# transAmpV1_sch.net
KiCad netlist of a schematic drawn in Altium Designer
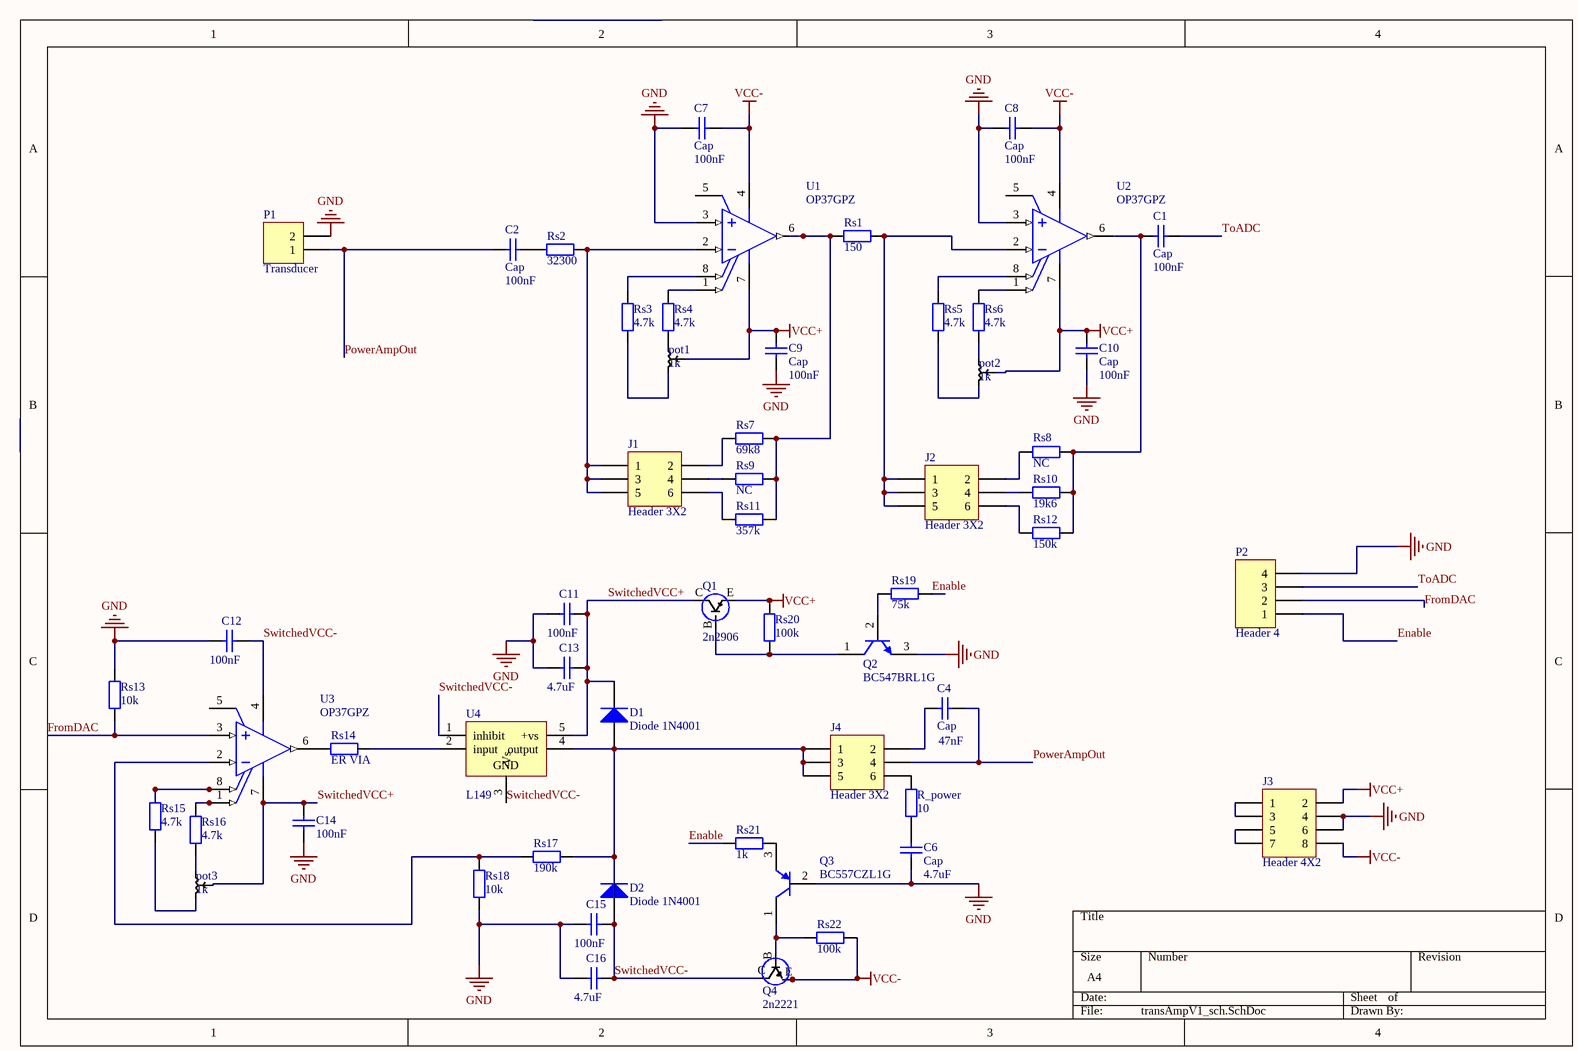
[diagram p0: transAmpV1_sch.SchDoc]

(export (version "E")
  (design (tool "Eeschema 10.0.6"))
  (components
    (comp (ref "C1")
      (value "Cap")
      (footprint "RAD-0.2  PCBK")
      (description "Capacitor")
      (fields (field (name "ALTIUM_VALUE") "100nF") (field (name "PUBLISHER") "Altium Limited"))
      (libsource (lib "pcb_kursus_lib2020") (part "Cap PCBK"))
    )
    (comp (ref "C2")
      (value "Cap")
      (footprint "RAD-0.2  PCBK")
      (description "Capacitor")
      (fields (field (name "ALTIUM_VALUE") "100nF") (field (name "PUBLISHER") "Altium Limited"))
      (libsource (lib "pcb_kursus_lib2020") (part "Cap PCBK"))
    )
    (comp (ref "C4")
      (value "Cap")
      (footprint "RAD-0.2  PCBK")
      (description "Capacitor")
      (fields (field (name "ALTIUM_VALUE") "47nF") (field (name "PUBLISHER") "Altium Limited"))
      (libsource (lib "pcb_kursus_lib2020") (part "Cap PCBK"))
    )
    (comp (ref "C6")
      (value "Cap")
      (footprint "RAD-0.2  PCBK")
      (description "Capacitor")
      (fields (field (name "ALTIUM_VALUE") "4.7uF") (field (name "PUBLISHER") "Altium Limited"))
      (libsource (lib "pcb_kursus_lib2020") (part "Cap PCBK"))
    )
    (comp (ref "C7")
      (value "Cap")
      (footprint "RAD-0.2  PCBK")
      (description "Capacitor")
      (fields (field (name "ALTIUM_VALUE") "100nF") (field (name "PUBLISHER") "Altium Limited"))
      (libsource (lib "pcb_kursus_lib2020") (part "Cap PCBK"))
    )
    (comp (ref "C8")
      (value "Cap")
      (footprint "RAD-0.2  PCBK")
      (description "Capacitor")
      (fields (field (name "ALTIUM_VALUE") "100nF") (field (name "PUBLISHER") "Altium Limited"))
      (libsource (lib "pcb_kursus_lib2020") (part "Cap PCBK"))
    )
    (comp (ref "C9")
      (value "Cap")
      (footprint "RAD-0.2  PCBK")
      (description "Capacitor")
      (fields (field (name "ALTIUM_VALUE") "100nF") (field (name "PUBLISHER") "Altium Limited"))
      (libsource (lib "pcb_kursus_lib2020") (part "Cap PCBK"))
    )
    (comp (ref "C10")
      (value "Cap")
      (footprint "RAD-0.2  PCBK")
      (description "Capacitor")
      (fields (field (name "ALTIUM_VALUE") "100nF") (field (name "PUBLISHER") "Altium Limited"))
      (libsource (lib "pcb_kursus_lib2020") (part "Cap PCBK"))
    )
    (comp (ref "C11")
      (value "100nF")
      (footprint "RAD-0.2  PCBK")
      (description "Capacitor")
      (fields (field (name "Comment") "Cap") (field (name "PUBLISHER") "Altium Limited"))
      (libsource (lib "pcb_kursus_lib2020") (part "Cap PCBK"))
    )
    (comp (ref "C12")
      (value "100nF")
      (footprint "RAD-0.2  PCBK")
      (description "Capacitor")
      (fields (field (name "Comment") "Cap") (field (name "PUBLISHER") "Altium Limited"))
      (libsource (lib "pcb_kursus_lib2020") (part "Cap PCBK"))
    )
    (comp (ref "C13")
      (value "4.7uF")
      (footprint "RAD-0.2  PCBK")
      (description "Capacitor")
      (fields (field (name "Comment") "Cap") (field (name "PUBLISHER") "Altium Limited"))
      (libsource (lib "pcb_kursus_lib2020") (part "Cap PCBK"))
    )
    (comp (ref "C14")
      (value "100nF")
      (footprint "RAD-0.2  PCBK")
      (description "Capacitor")
      (fields (field (name "Comment") "Cap") (field (name "PUBLISHER") "Altium Limited"))
      (libsource (lib "pcb_kursus_lib2020") (part "Cap PCBK"))
    )
    (comp (ref "C15")
      (value "100nF")
      (footprint "RAD-0.2  PCBK")
      (description "Capacitor")
      (fields (field (name "Comment") "Cap") (field (name "PUBLISHER") "Altium Limited"))
      (libsource (lib "pcb_kursus_lib2020") (part "Cap PCBK"))
    )
    (comp (ref "C16")
      (value "4.7uF")
      (footprint "RAD-0.2  PCBK")
      (description "Capacitor")
      (fields (field (name "Comment") "Cap") (field (name "PUBLISHER") "Altium Limited"))
      (libsource (lib "pcb_kursus_lib2020") (part "Cap PCBK"))
    )
    (comp (ref "D1")
      (value "Diode 1N4001")
      (footprint "DO-41")
      (description "1 Amp General Purpose Rectifier")
      (fields (field (name "PUBLISHER") "Altium Limited"))
      (libsource (lib "Miscellaneous Devices") (part "Diode 1N4001"))
    )
    (comp (ref "D2")
      (value "Diode 1N4001")
      (footprint "DO-41")
      (description "1 Amp General Purpose Rectifier")
      (fields (field (name "PUBLISHER") "Altium Limited"))
      (libsource (lib "Miscellaneous Devices") (part "Diode 1N4001"))
    )
    (comp (ref "J1")
      (value "Header 3X2")
      (footprint "HDR2X3 PCBK")
      (description "Header, 3-Pin, Dual row")
      (fields (field (name "PUBLISHER") "Altium Limited"))
      (libsource (lib "pcb_kursus_lib2020") (part "Header 3X2 PBCK"))
    )
    (comp (ref "J2")
      (value "Header 3X2")
      (footprint "HDR2X3 PCBK")
      (description "Header, 3-Pin, Dual row")
      (fields (field (name "PUBLISHER") "Altium Limited"))
      (libsource (lib "pcb_kursus_lib2020") (part "Header 3X2 PBCK"))
    )
    (comp (ref "J3")
      (value "Header 4X2")
      (footprint "HDR2X4 PCBK")
      (description "Header, 4-Pin, Dual row")
      (fields (field (name "PUBLISHER") "Altium Limited"))
      (libsource (lib "pcb_kursus_lib2020") (part "Header 4X2 PBCK"))
    )
    (comp (ref "J4")
      (value "Header 3X2")
      (footprint "HDR2X3 PCBK")
      (description "Header, 3-Pin, Dual row")
      (fields (field (name "PUBLISHER") "Altium Limited"))
      (libsource (lib "pcb_kursus_lib2020") (part "Header 3X2 PBCK"))
    )
    (comp (ref "P1")
      (value "Transducer")
      (footprint "HDR1X2")
      (description "Header, 2-Pin")
      (fields (field (name "PUBLISHER") "Altium Limited"))
      (libsource (lib "Miscellaneous Connectors") (part "Header 2"))
    )
    (comp (ref "P2")
      (value "Header 4")
      (footprint "HDR1X4")
      (description "Header, 4-Pin")
      (fields (field (name "PUBLISHER") "Altium Limited"))
      (libsource (lib "Miscellaneous Connectors") (part "Header 4"))
    )
    (comp (ref "pot1")
      (value "1k")
      (footprint "potMeter_3328P")
      (libsource (lib "WatsonInt_Lib") (part "TrimPotOpAmp"))
    )
    (comp (ref "pot2")
      (value "1k")
      (footprint "potMeter_3328P")
      (libsource (lib "WatsonInt_Lib") (part "TrimPotOpAmp"))
    )
    (comp (ref "pot3")
      (value "1k")
      (footprint "potMeter_3328P")
      (libsource (lib "WatsonInt_Lib") (part "TrimPotOpAmp"))
    )
    (comp (ref "Q1") (value "2n2906") (footprint "TO-18") (libsource (lib "WatsonInt_Lib") (part "2n2906")))
    (comp (ref "Q2")
      (value "BC547BRL1G")
      (footprint "ONSC-TO-92-3-29-11_AM_BL")
      (description "Amplifier Transistor, NPN Silicon, 3-Pin TO-92, Pb-Free, Tape and Reel")
      (fields (field (name "MANUFACTURER") "On Semiconductor"))
      (libsource (lib "Altium Content Vault") (part "ONSC-NPN-C1B2E3-3"))
    )
    (comp (ref "Q3")
      (value "BC557CZL1G")
      (footprint "ONSC-TO-92-3-29-11_AM_BL")
      (description "Amplifier Transistor, PNP Silicon, 3-Pin TO-92, Pb-Free, Ammo Box")
      (fields (field (name "MANUFACTURER") "On Semiconductor"))
      (libsource (lib "Altium Content Vault") (part "ONSC-PNP-C1B2E3-3"))
    )
    (comp (ref "Q4") (value "2n2221") (footprint "TO-18") (libsource (lib "WatsonInt_Lib") (part "2n2221")))
    (comp (ref "Rs1")
      (value "150")
      (footprint "AXIAL-0.4 PCBK")
      (description "Resistor")
      (fields (field (name "PUBLISHER") "Altium Limited"))
      (libsource (lib "pcb_kursus_lib2020") (part "Res PCBK"))
    )
    (comp (ref "Rs2")
      (value "32300")
      (footprint "AXIAL-0.4 PCBK")
      (description "Resistor")
      (fields (field (name "PUBLISHER") "Altium Limited"))
      (libsource (lib "pcb_kursus_lib2020") (part "Res PCBK"))
    )
    (comp (ref "Rs3")
      (value "4.7k")
      (footprint "AXIAL-0.4 PCBK")
      (description "Resistor")
      (fields (field (name "PUBLISHER") "Altium Limited"))
      (libsource (lib "") (part "Res PCBK_1"))
    )
    (comp (ref "Rs4")
      (value "4.7k")
      (footprint "AXIAL-0.4 PCBK")
      (description "Resistor")
      (fields (field (name "PUBLISHER") "Altium Limited"))
      (libsource (lib "") (part "Res PCBK_1"))
    )
    (comp (ref "Rs5")
      (value "4.7k")
      (footprint "AXIAL-0.4 PCBK")
      (description "Resistor")
      (fields (field (name "PUBLISHER") "Altium Limited"))
      (libsource (lib "") (part "Res PCBK_1"))
    )
    (comp (ref "Rs6")
      (value "4.7k")
      (footprint "AXIAL-0.4 PCBK")
      (description "Resistor")
      (fields (field (name "PUBLISHER") "Altium Limited"))
      (libsource (lib "") (part "Res PCBK_1"))
    )
    (comp (ref "Rs7")
      (value "69k8")
      (footprint "AXIAL-0.4 PCBK")
      (description "Resistor")
      (fields (field (name "PUBLISHER") "Altium Limited"))
      (libsource (lib "pcb_kursus_lib2020") (part "Res PCBK"))
    )
    (comp (ref "Rs8")
      (value "NC")
      (footprint "AXIAL-0.4 PCBK")
      (description "Resistor")
      (fields (field (name "PUBLISHER") "Altium Limited"))
      (libsource (lib "pcb_kursus_lib2020") (part "Res PCBK"))
    )
    (comp (ref "Rs9")
      (value "NC")
      (footprint "AXIAL-0.4 PCBK")
      (description "Resistor")
      (fields (field (name "PUBLISHER") "Altium Limited"))
      (libsource (lib "pcb_kursus_lib2020") (part "Res PCBK"))
    )
    (comp (ref "Rs10")
      (value "19k6")
      (footprint "AXIAL-0.4 PCBK")
      (description "Resistor")
      (fields (field (name "PUBLISHER") "Altium Limited"))
      (libsource (lib "pcb_kursus_lib2020") (part "Res PCBK"))
    )
    (comp (ref "Rs11")
      (value "357k")
      (footprint "AXIAL-0.4 PCBK")
      (description "Resistor")
      (fields (field (name "PUBLISHER") "Altium Limited"))
      (libsource (lib "pcb_kursus_lib2020") (part "Res PCBK"))
    )
    (comp (ref "Rs12")
      (value "150k")
      (footprint "AXIAL-0.4 PCBK")
      (description "Resistor")
      (fields (field (name "PUBLISHER") "Altium Limited"))
      (libsource (lib "pcb_kursus_lib2020") (part "Res PCBK"))
    )
    (comp (ref "Rs13")
      (value "10k")
      (footprint "AXIAL-0.4 PCBK")
      (description "Resistor")
      (fields (field (name "PUBLISHER") "Altium Limited"))
      (libsource (lib "") (part "Res PCBK_2"))
    )
    (comp (ref "Rs14")
      (value "ER VIA")
      (footprint "AXIAL-0.4 PCBK")
      (description "Resistor")
      (fields (field (name "PUBLISHER") "Altium Limited"))
      (libsource (lib "pcb_kursus_lib2020") (part "Res PCBK"))
    )
    (comp (ref "Rs15")
      (value "4.7k")
      (footprint "AXIAL-0.4 PCBK")
      (description "Resistor")
      (fields (field (name "PUBLISHER") "Altium Limited"))
      (libsource (lib "") (part "Res PCBK_1"))
    )
    (comp (ref "Rs16")
      (value "4.7k")
      (footprint "AXIAL-0.4 PCBK")
      (description "Resistor")
      (fields (field (name "PUBLISHER") "Altium Limited"))
      (libsource (lib "") (part "Res PCBK_1"))
    )
    (comp (ref "Rs17")
      (value "190k")
      (footprint "AXIAL-0.4 PCBK")
      (description "Resistor")
      (fields (field (name "PUBLISHER") "Altium Limited"))
      (libsource (lib "pcb_kursus_lib2020") (part "Res PCBK"))
    )
    (comp (ref "Rs18")
      (value "10k")
      (footprint "AXIAL-0.4 PCBK")
      (description "Resistor")
      (fields (field (name "PUBLISHER") "Altium Limited"))
      (libsource (lib "") (part "Res PCBK_2"))
    )
    (comp (ref "Rs19")
      (value "75k")
      (footprint "AXIAL-0.4 PCBK")
      (description "Resistor")
      (fields (field (name "PUBLISHER") "Altium Limited"))
      (libsource (lib "pcb_kursus_lib2020") (part "Res PCBK"))
    )
    (comp (ref "Rs20")
      (value "100k")
      (footprint "AXIAL-0.4 PCBK")
      (description "Resistor")
      (fields (field (name "PUBLISHER") "Altium Limited"))
      (libsource (lib "") (part "Res PCBK_1"))
    )
    (comp (ref "Rs21")
      (value "1k")
      (footprint "AXIAL-0.4 PCBK")
      (description "Resistor")
      (fields (field (name "PUBLISHER") "Altium Limited"))
      (libsource (lib "pcb_kursus_lib2020") (part "Res PCBK"))
    )
    (comp (ref "Rs22")
      (value "100k")
      (footprint "AXIAL-0.4 PCBK")
      (description "Resistor")
      (fields (field (name "PUBLISHER") "Altium Limited"))
      (libsource (lib "") (part "Res PCBK_3"))
    )
    (comp (ref "R_power")
      (value "10")
      (footprint "AXIAL-0.4 PCBK")
      (description "Resistor")
      (fields (field (name "PUBLISHER") "Altium Limited"))
      (libsource (lib "") (part "Res PCBK_2"))
    )
    (comp (ref "U1")
      (value "OP37GPZ")
      (footprint "ADI-N-8")
      (fields (field (name "GENERIC PART NUMBER") "OP37") (field (name "MANUFACTURER") "Analog Devices"))
      (libsource (lib "Altium Content Vault") (part "ADI-OP177_X7-8"))
    )
    (comp (ref "U2")
      (value "OP37GPZ")
      (footprint "ADI-N-8")
      (fields (field (name "GENERIC PART NUMBER") "OP37") (field (name "MANUFACTURER") "Analog Devices"))
      (libsource (lib "Altium Content Vault") (part "ADI-OP177_X7-8"))
    )
    (comp (ref "U3")
      (value "OP37GPZ")
      (footprint "ADI-N-8")
      (fields (field (name "GENERIC PART NUMBER") "OP37") (field (name "MANUFACTURER") "Analog Devices"))
      (libsource (lib "Altium Content Vault") (part "ADI-OP177_X7-8"))
    )
    (comp (ref "U4")
      (value "L149")
      (footprint "PentawattV")
      (description "Adjustable Voltage and Current Regulator, 5-Pin Pentawatt, Tube")
      (libsource (lib "Altium Content Vault") (part "PM-REG-L200-ZIL5"))
    )
  )
  (nets
    (net (code "1") (name "/Enable") (class "Default")
      (node (ref "P2") (pin "1") (pinfunction "1_1") (pintype "passive"))
      (node (ref "Rs19") (pin "1") (pinfunction "1_1") (pintype "passive"))
      (node (ref "Rs21") (pin "2") (pinfunction "2_2") (pintype "passive"))
    )
    (net (code "2") (name "/FromDAC") (class "Default")
      (node (ref "P2") (pin "2") (pinfunction "2_2") (pintype "passive"))
      (node (ref "Rs13") (pin "2") (pinfunction "2_2") (pintype "passive"))
      (node (ref "U3") (pin "3") (pinfunction "+IN_3") (pintype "input"))
    )
    (net (code "3") (name "/PowerAmpOut") (class "Default")
      (node (ref "C2") (pin "1") (pinfunction "1_1") (pintype "passive"))
      (node (ref "C4") (pin "2") (pinfunction "2_2") (pintype "passive"))
      (node (ref "J4") (pin "4") (pinfunction "4_4") (pintype "passive"))
      (node (ref "P1") (pin "1") (pinfunction "1_1") (pintype "passive"))
    )
    (net (code "4") (name "/SwitchedVCC+") (class "Default")
      (node (ref "C11") (pin "2") (pinfunction "2_2") (pintype "passive"))
      (node (ref "C13") (pin "2") (pinfunction "2_2") (pintype "passive"))
      (node (ref "C14") (pin "2") (pinfunction "2_2") (pintype "passive"))
      (node (ref "D1") (pin "2") (pinfunction "K_2") (pintype "passive"))
      (node (ref "Q1") (pin "C") (pinfunction "22_C") (pintype "passive"))
      (node (ref "U3") (pin "7") (pinfunction "V+_7") (pintype "power_in"))
      (node (ref "U4") (pin "5") (pinfunction "+vs_5") (pintype "power_in"))
      (node (ref "pot3") (pin "2") (pinfunction "2_2") (pintype "passive"))
    )
    (net (code "5") (name "/SwitchedVCC-") (class "Default")
      (node (ref "C12") (pin "2") (pinfunction "2_2") (pintype "passive"))
      (node (ref "C15") (pin "2") (pinfunction "2_2") (pintype "passive"))
      (node (ref "C16") (pin "2") (pinfunction "2_2") (pintype "passive"))
      (node (ref "D2") (pin "1") (pinfunction "A_1") (pintype "passive"))
      (node (ref "Q4") (pin "C") (pinfunction "23_C") (pintype "passive"))
      (node (ref "U3") (pin "4") (pinfunction "V-_4") (pintype "power_in"))
      (node (ref "U4") (pin "1") (pinfunction "inhibit_1") (pintype "power_in"))
      (node (ref "U4") (pin "3") (pinfunction "-Vs_3") (pintype "power_in"))
    )
    (net (code "6") (name "/ToADC") (class "Default")
      (node (ref "C1") (pin "2") (pinfunction "2_2") (pintype "passive"))
      (node (ref "P2") (pin "3") (pinfunction "3_3") (pintype "passive"))
    )
    (net (code "7") (name "GND") (class "Default")
      (node (ref "C10") (pin "2") (pinfunction "2_2") (pintype "passive"))
      (node (ref "C11") (pin "1") (pinfunction "1_1") (pintype "passive"))
      (node (ref "C12") (pin "1") (pinfunction "1_1") (pintype "passive"))
      (node (ref "C13") (pin "1") (pinfunction "1_1") (pintype "passive"))
      (node (ref "C14") (pin "1") (pinfunction "1_1") (pintype "passive"))
      (node (ref "C15") (pin "1") (pinfunction "1_1") (pintype "passive"))
      (node (ref "C16") (pin "1") (pinfunction "1_1") (pintype "passive"))
      (node (ref "C6") (pin "2") (pinfunction "2_2") (pintype "passive"))
      (node (ref "C7") (pin "1") (pinfunction "1_1") (pintype "passive"))
      (node (ref "C8") (pin "1") (pinfunction "1_1") (pintype "passive"))
      (node (ref "C9") (pin "2") (pinfunction "2_2") (pintype "passive"))
      (node (ref "J3") (pin "4") (pinfunction "4_4") (pintype "passive"))
      (node (ref "J3") (pin "6") (pinfunction "6_6") (pintype "passive"))
      (node (ref "P1") (pin "2") (pinfunction "2_2") (pintype "passive"))
      (node (ref "P2") (pin "4") (pinfunction "4_4") (pintype "passive"))
      (node (ref "Q2") (pin "3") (pinfunction "E_3") (pintype "passive"))
      (node (ref "Q3") (pin "2") (pinfunction "B_2") (pintype "passive"))
      (node (ref "Rs13") (pin "1") (pinfunction "1_1") (pintype "passive"))
      (node (ref "Rs18") (pin "2") (pinfunction "2_2") (pintype "passive"))
      (node (ref "U1") (pin "3") (pinfunction "+IN_3") (pintype "input"))
      (node (ref "U2") (pin "3") (pinfunction "+IN_3") (pintype "input"))
    )
    (net (code "8") (name "Net-(C2-Pad2)") (class "Default")
      (node (ref "C2") (pin "2") (pinfunction "2_2") (pintype "passive"))
      (node (ref "Rs2") (pin "2") (pinfunction "2_2") (pintype "passive"))
    )
    (net (code "9") (name "Net-(C4-Pad1)") (class "Default")
      (node (ref "C4") (pin "1") (pinfunction "1_1") (pintype "passive"))
      (node (ref "J4") (pin "2") (pinfunction "2_2") (pintype "passive"))
    )
    (net (code "10") (name "Net-(C6-Pad1)") (class "Default")
      (node (ref "C6") (pin "1") (pinfunction "1_1") (pintype "passive"))
      (node (ref "R_power") (pin "2") (pinfunction "2_2") (pintype "passive"))
    )
    (net (code "11") (name "Net-(D1-A)") (class "Default")
      (node (ref "D1") (pin "1") (pinfunction "A_1") (pintype "passive"))
      (node (ref "D2") (pin "2") (pinfunction "K_2") (pintype "passive"))
      (node (ref "J4") (pin "1") (pinfunction "1_1") (pintype "passive"))
      (node (ref "J4") (pin "3") (pinfunction "3_3") (pintype "passive"))
      (node (ref "J4") (pin "5") (pinfunction "5_5") (pintype "passive"))
      (node (ref "Rs17") (pin "1") (pinfunction "1_1") (pintype "passive"))
      (node (ref "U4") (pin "4") (pinfunction "output_4") (pintype "passive"))
    )
    (net (code "12") (name "Net-(J1-Pad2)") (class "Default")
      (node (ref "J1") (pin "2") (pinfunction "2_2") (pintype "passive"))
      (node (ref "Rs7") (pin "2") (pinfunction "2_2") (pintype "passive"))
    )
    (net (code "13") (name "Net-(J1-Pad4)") (class "Default")
      (node (ref "J1") (pin "4") (pinfunction "4_4") (pintype "passive"))
      (node (ref "Rs9") (pin "2") (pinfunction "2_2") (pintype "passive"))
    )
    (net (code "14") (name "Net-(J1-Pad6)") (class "Default")
      (node (ref "J1") (pin "6") (pinfunction "6_6") (pintype "passive"))
      (node (ref "Rs11") (pin "2") (pinfunction "2_2") (pintype "passive"))
    )
    (net (code "15") (name "Net-(J2-Pad2)") (class "Default")
      (node (ref "J2") (pin "2") (pinfunction "2_2") (pintype "passive"))
      (node (ref "Rs8") (pin "2") (pinfunction "2_2") (pintype "passive"))
    )
    (net (code "16") (name "Net-(J2-Pad4)") (class "Default")
      (node (ref "J2") (pin "4") (pinfunction "4_4") (pintype "passive"))
      (node (ref "Rs10") (pin "2") (pinfunction "2_2") (pintype "passive"))
    )
    (net (code "17") (name "Net-(J2-Pad6)") (class "Default")
      (node (ref "J2") (pin "6") (pinfunction "6_6") (pintype "passive"))
      (node (ref "Rs12") (pin "2") (pinfunction "2_2") (pintype "passive"))
    )
    (net (code "18") (name "Net-(J3-Pad1)") (class "Default")
      (node (ref "J3") (pin "1") (pinfunction "1_1") (pintype "passive"))
      (node (ref "J3") (pin "3") (pinfunction "3_3") (pintype "passive"))
    )
    (net (code "19") (name "Net-(J3-Pad5)") (class "Default")
      (node (ref "J3") (pin "5") (pinfunction "5_5") (pintype "passive"))
      (node (ref "J3") (pin "7") (pinfunction "7_7") (pintype "passive"))
    )
    (net (code "20") (name "Net-(J4-Pad6)") (class "Default")
      (node (ref "J4") (pin "6") (pinfunction "6_6") (pintype "passive"))
      (node (ref "R_power") (pin "1") (pinfunction "1_1") (pintype "passive"))
    )
    (net (code "21") (name "Net-(Q2-B)") (class "Default")
      (node (ref "Q2") (pin "2") (pinfunction "B_2") (pintype "passive"))
      (node (ref "Rs19") (pin "2") (pinfunction "2_2") (pintype "passive"))
    )
    (net (code "22") (name "Net-(Q2-C)") (class "Default")
      (node (ref "Q1") (pin "B") (pintype "passive"))
      (node (ref "Q2") (pin "1") (pinfunction "C_1") (pintype "passive"))
      (node (ref "Rs20") (pin "1") (pinfunction "1_1") (pintype "passive"))
    )
    (net (code "23") (name "Net-(Q3-C)") (class "Default")
      (node (ref "Q3") (pin "1") (pinfunction "C_1") (pintype "passive"))
      (node (ref "Q4") (pin "B") (pintype "passive"))
      (node (ref "Rs22") (pin "1") (pinfunction "1_1") (pintype "passive"))
    )
    (net (code "24") (name "Net-(Q3-E)") (class "Default")
      (node (ref "Q3") (pin "3") (pinfunction "E_3") (pintype "passive"))
      (node (ref "Rs21") (pin "1") (pinfunction "1_1") (pintype "passive"))
    )
    (net (code "25") (name "Net-(Rs3-Pad1)") (class "Default")
      (node (ref "Rs3") (pin "1") (pinfunction "1_1") (pintype "passive"))
      (node (ref "pot1") (pin "3") (pinfunction "3_3") (pintype "passive"))
    )
    (net (code "26") (name "Net-(Rs3-Pad2)") (class "Default")
      (node (ref "Rs3") (pin "2") (pinfunction "2_2") (pintype "passive"))
      (node (ref "U1") (pin "8") (pinfunction "VOS_TRIM_8") (pintype "input"))
    )
    (net (code "27") (name "Net-(Rs4-Pad1)") (class "Default")
      (node (ref "Rs4") (pin "1") (pinfunction "1_1") (pintype "passive"))
      (node (ref "pot1") (pin "1") (pinfunction "1_1") (pintype "passive"))
    )
    (net (code "28") (name "Net-(Rs4-Pad2)") (class "Default")
      (node (ref "Rs4") (pin "2") (pinfunction "2_2") (pintype "passive"))
      (node (ref "U1") (pin "1") (pinfunction "VOS_TRIM_1") (pintype "input"))
    )
    (net (code "29") (name "Net-(Rs5-Pad1)") (class "Default")
      (node (ref "Rs5") (pin "1") (pinfunction "1_1") (pintype "passive"))
      (node (ref "pot2") (pin "3") (pinfunction "3_3") (pintype "passive"))
    )
    (net (code "30") (name "Net-(Rs5-Pad2)") (class "Default")
      (node (ref "Rs5") (pin "2") (pinfunction "2_2") (pintype "passive"))
      (node (ref "U2") (pin "8") (pinfunction "VOS_TRIM_8") (pintype "input"))
    )
    (net (code "31") (name "Net-(Rs6-Pad1)") (class "Default")
      (node (ref "Rs6") (pin "1") (pinfunction "1_1") (pintype "passive"))
      (node (ref "pot2") (pin "1") (pinfunction "1_1") (pintype "passive"))
    )
    (net (code "32") (name "Net-(Rs6-Pad2)") (class "Default")
      (node (ref "Rs6") (pin "2") (pinfunction "2_2") (pintype "passive"))
      (node (ref "U2") (pin "1") (pinfunction "VOS_TRIM_1") (pintype "input"))
    )
    (net (code "33") (name "Net-(Rs15-Pad1)") (class "Default")
      (node (ref "Rs15") (pin "1") (pinfunction "1_1") (pintype "passive"))
      (node (ref "pot3") (pin "3") (pinfunction "3_3") (pintype "passive"))
    )
    (net (code "34") (name "Net-(Rs15-Pad2)") (class "Default")
      (node (ref "Rs15") (pin "2") (pinfunction "2_2") (pintype "passive"))
      (node (ref "U3") (pin "8") (pinfunction "VOS_TRIM_8") (pintype "input"))
    )
    (net (code "35") (name "Net-(Rs16-Pad1)") (class "Default")
      (node (ref "Rs16") (pin "1") (pinfunction "1_1") (pintype "passive"))
      (node (ref "pot3") (pin "1") (pinfunction "1_1") (pintype "passive"))
    )
    (net (code "36") (name "Net-(Rs16-Pad2)") (class "Default")
      (node (ref "Rs16") (pin "2") (pinfunction "2_2") (pintype "passive"))
      (node (ref "U3") (pin "1") (pinfunction "VOS_TRIM_1") (pintype "input"))
    )
    (net (code "37") (name "Net-(U1--IN)") (class "Default")
      (node (ref "J1") (pin "1") (pinfunction "1_1") (pintype "passive"))
      (node (ref "J1") (pin "3") (pinfunction "3_3") (pintype "passive"))
      (node (ref "J1") (pin "5") (pinfunction "5_5") (pintype "passive"))
      (node (ref "Rs2") (pin "1") (pinfunction "1_1") (pintype "passive"))
      (node (ref "U1") (pin "2") (pinfunction "-IN_2") (pintype "input"))
    )
    (net (code "38") (name "Net-(U1-OUT)") (class "Default")
      (node (ref "Rs1") (pin "2") (pinfunction "2_2") (pintype "passive"))
      (node (ref "Rs11") (pin "1") (pinfunction "1_1") (pintype "passive"))
      (node (ref "Rs7") (pin "1") (pinfunction "1_1") (pintype "passive"))
      (node (ref "Rs9") (pin "1") (pinfunction "1_1") (pintype "passive"))
      (node (ref "U1") (pin "6") (pinfunction "OUT_6") (pintype "output"))
    )
    (net (code "39") (name "Net-(U2--IN)") (class "Default")
      (node (ref "J2") (pin "1") (pinfunction "1_1") (pintype "passive"))
      (node (ref "J2") (pin "3") (pinfunction "3_3") (pintype "passive"))
      (node (ref "J2") (pin "5") (pinfunction "5_5") (pintype "passive"))
      (node (ref "Rs1") (pin "1") (pinfunction "1_1") (pintype "passive"))
      (node (ref "U2") (pin "2") (pinfunction "-IN_2") (pintype "input"))
    )
    (net (code "40") (name "Net-(U2-OUT)") (class "Default")
      (node (ref "C1") (pin "1") (pinfunction "1_1") (pintype "passive"))
      (node (ref "Rs10") (pin "1") (pinfunction "1_1") (pintype "passive"))
      (node (ref "Rs12") (pin "1") (pinfunction "1_1") (pintype "passive"))
      (node (ref "Rs8") (pin "1") (pinfunction "1_1") (pintype "passive"))
      (node (ref "U2") (pin "6") (pinfunction "OUT_6") (pintype "output"))
    )
    (net (code "41") (name "Net-(U3--IN)") (class "Default")
      (node (ref "Rs17") (pin "2") (pinfunction "2_2") (pintype "passive"))
      (node (ref "Rs18") (pin "1") (pinfunction "1_1") (pintype "passive"))
      (node (ref "U3") (pin "2") (pinfunction "-IN_2") (pintype "input"))
    )
    (net (code "42") (name "Net-(U3-OUT)") (class "Default")
      (node (ref "Rs14") (pin "2") (pinfunction "2_2") (pintype "passive"))
      (node (ref "U3") (pin "6") (pinfunction "OUT_6") (pintype "output"))
    )
    (net (code "43") (name "Net-(U4-input)") (class "Default")
      (node (ref "Rs14") (pin "1") (pinfunction "1_1") (pintype "passive"))
      (node (ref "U4") (pin "2") (pinfunction "input_2") (pintype "passive"))
    )
    (net (code "44") (name "VCC+") (class "Default")
      (node (ref "C10") (pin "1") (pinfunction "1_1") (pintype "passive"))
      (node (ref "C9") (pin "1") (pinfunction "1_1") (pintype "passive"))
      (node (ref "J3") (pin "2") (pinfunction "2_2") (pintype "passive"))
      (node (ref "Q1") (pin "E") (pinfunction "23_E") (pintype "passive"))
      (node (ref "Rs20") (pin "2") (pinfunction "2_2") (pintype "passive"))
      (node (ref "U1") (pin "7") (pinfunction "V+_7") (pintype "power_in"))
      (node (ref "U2") (pin "7") (pinfunction "V+_7") (pintype "power_in"))
      (node (ref "pot1") (pin "2") (pinfunction "2_2") (pintype "passive"))
      (node (ref "pot2") (pin "2") (pinfunction "2_2") (pintype "passive"))
    )
    (net (code "45") (name "VCC-") (class "Default")
      (node (ref "C7") (pin "2") (pinfunction "2_2") (pintype "passive"))
      (node (ref "C8") (pin "2") (pinfunction "2_2") (pintype "passive"))
      (node (ref "J3") (pin "8") (pinfunction "8_8") (pintype "passive"))
      (node (ref "Q4") (pin "E") (pinfunction "22_E") (pintype "passive"))
      (node (ref "Rs22") (pin "2") (pinfunction "2_2") (pintype "passive"))
      (node (ref "U1") (pin "4") (pinfunction "V-_4") (pintype "power_in"))
      (node (ref "U2") (pin "4") (pinfunction "V-_4") (pintype "power_in"))
    )
    (net (code "46") (name "unconnected-(U1-NC-Pad5)") (class "Default")
      (node (ref "U1") (pin "5") (pinfunction "NC_5") (pintype "passive"))
    )
    (net (code "47") (name "unconnected-(U2-NC-Pad5)") (class "Default")
      (node (ref "U2") (pin "5") (pinfunction "NC_5") (pintype "passive"))
    )
    (net (code "48") (name "unconnected-(U3-NC-Pad5)") (class "Default")
      (node (ref "U3") (pin "5") (pinfunction "NC_5") (pintype "passive"))
    )
  )
)
